# SCH_USB-Converter_2025-04-09.net
KiCad netlist of a schematic drawn in EasyEDA
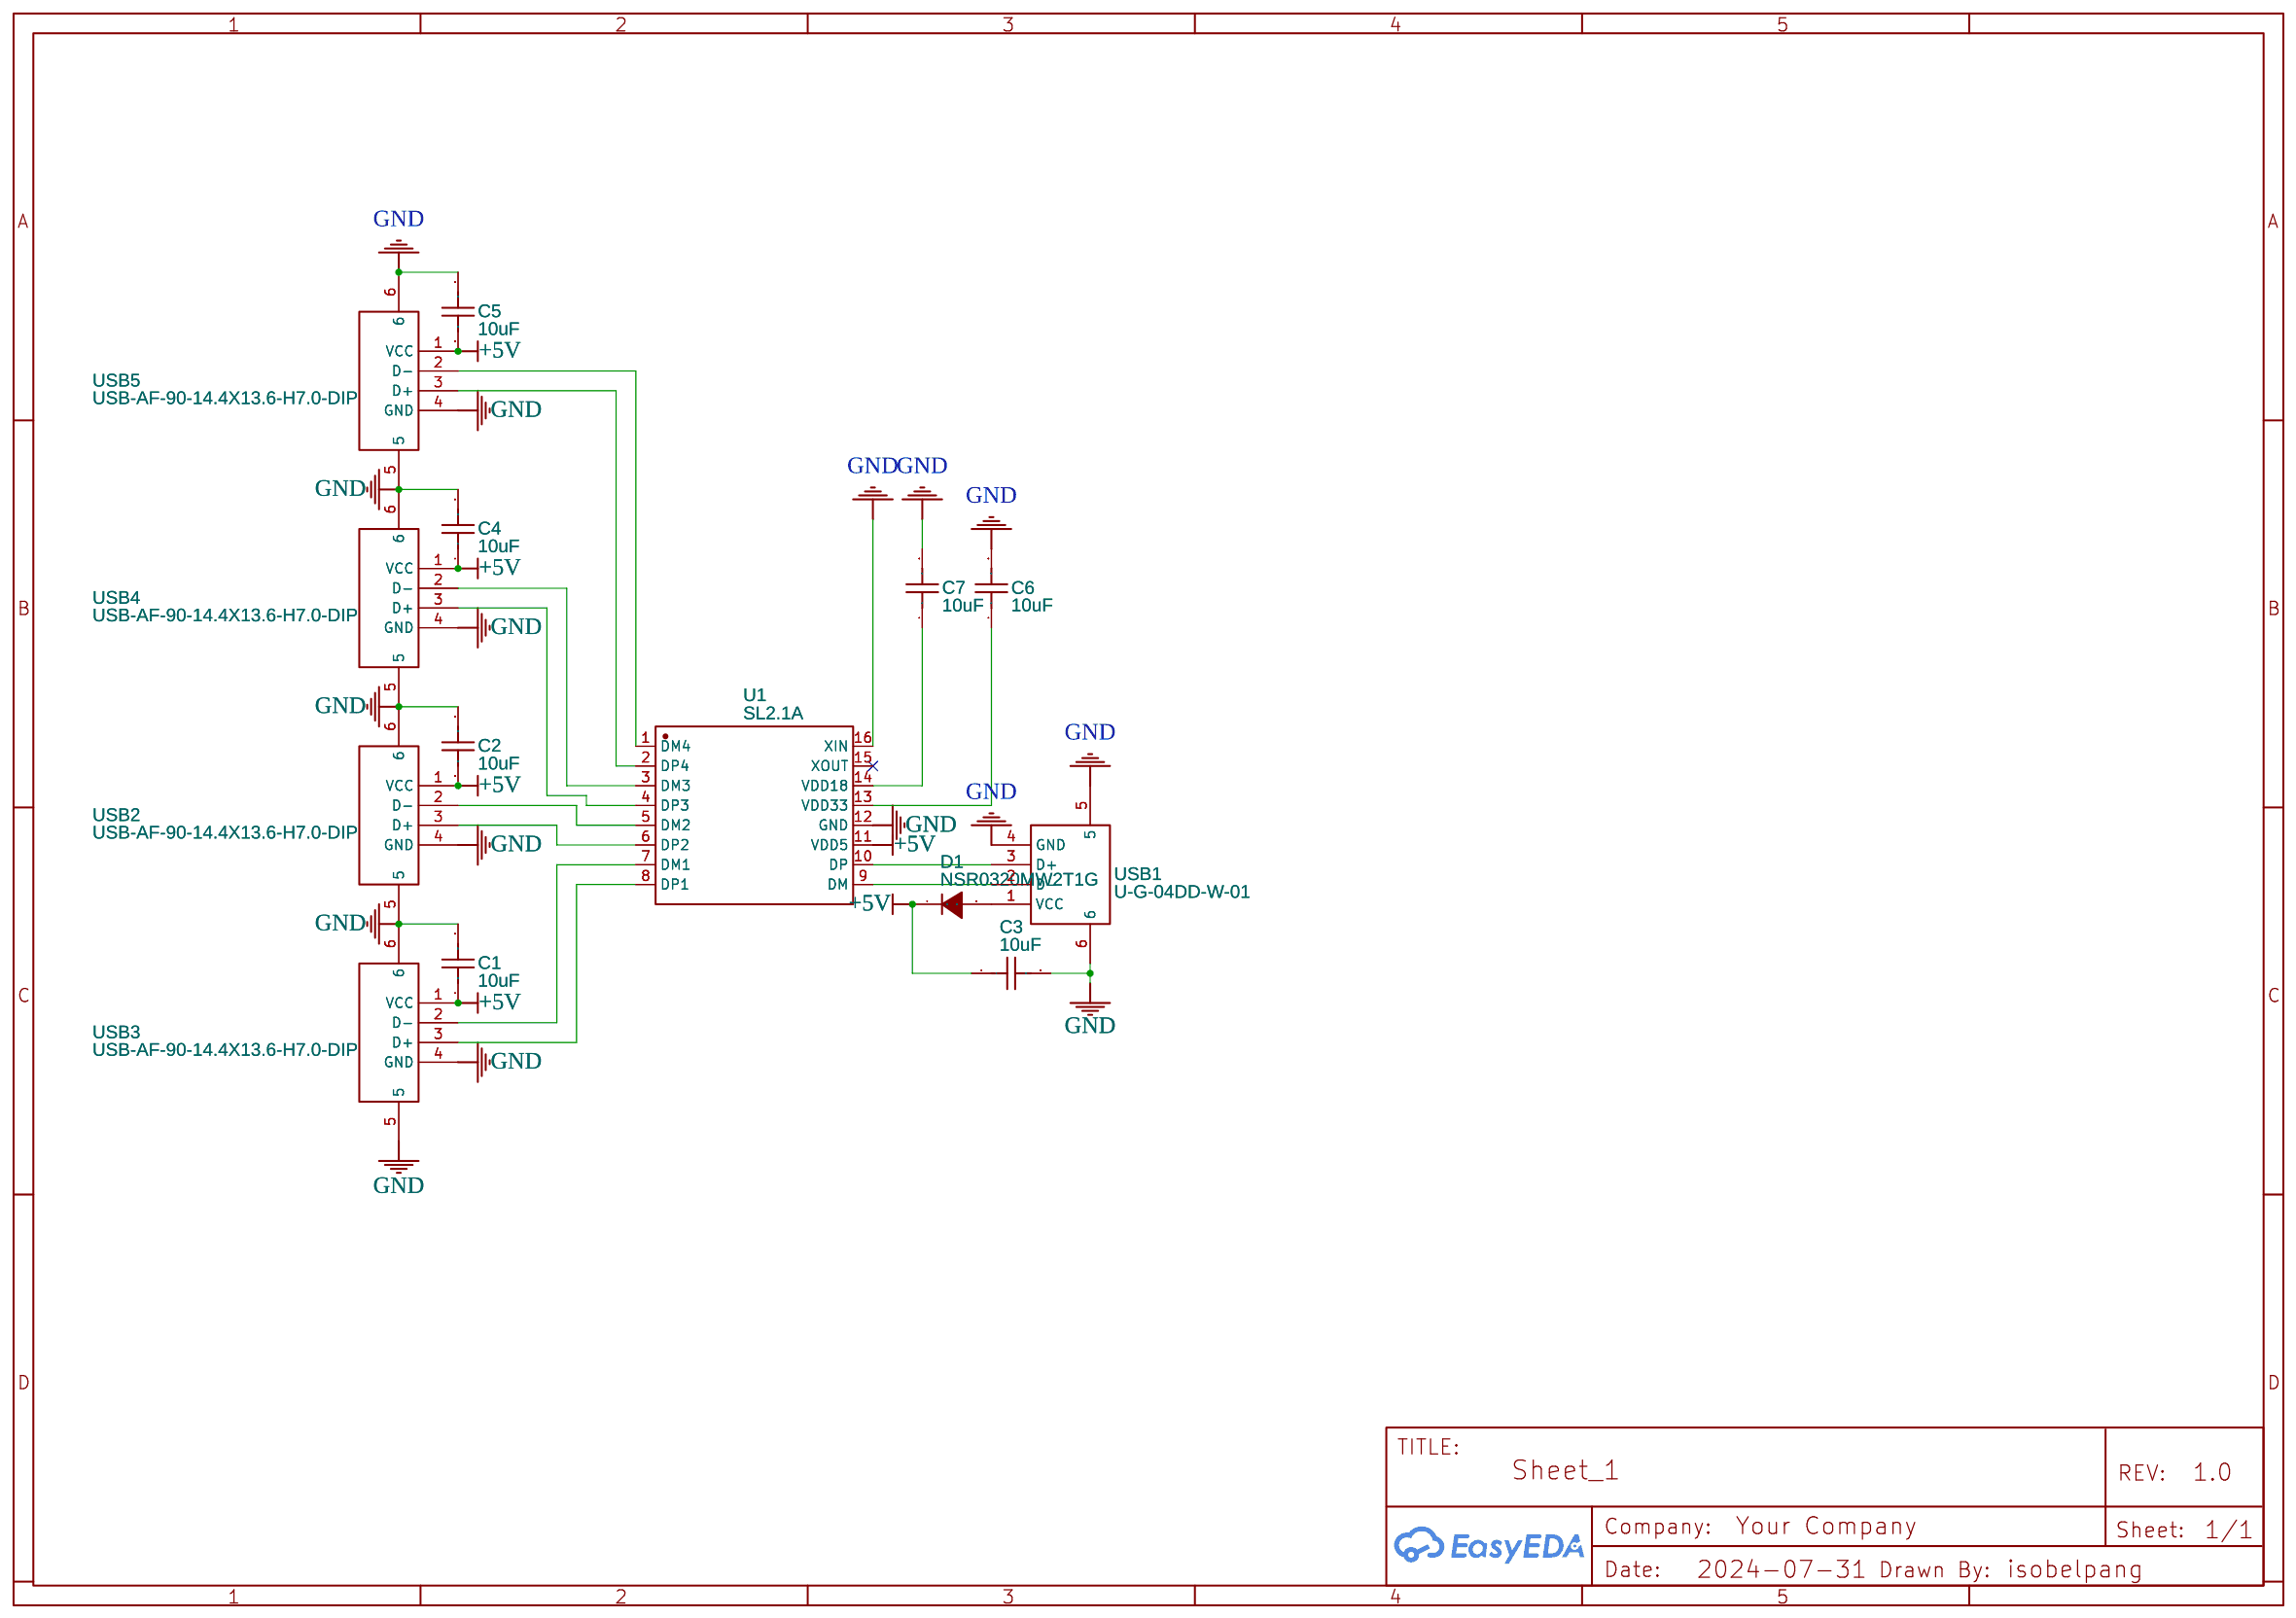
[diagram p0: schematic sheet]

(export (version "E")
  (design (tool "Eeschema 10.0.6"))
  (components
    (comp (ref "C1")
      (value "10uF")
      (fields
        (field (name "Manufacturer Part") "CL10A106KP8NNNC")
        (field (name "Manufacturer") "SAMSUNG(三星)")
      )
      (libsource (lib "") (part "CL10A106KP8NNNC"))
    )
    (comp (ref "C2")
      (value "10uF")
      (fields
        (field (name "Manufacturer Part") "CL10A106KP8NNNC")
        (field (name "Manufacturer") "SAMSUNG(三星)")
      )
      (libsource (lib "") (part "CL10A106KP8NNNC"))
    )
    (comp (ref "C3")
      (value "10uF")
      (fields
        (field (name "Manufacturer Part") "CL10A106KP8NNNC")
        (field (name "Manufacturer") "SAMSUNG(三星)")
      )
      (libsource (lib "") (part "CL10A106KP8NNNC_1"))
    )
    (comp (ref "C4")
      (value "10uF")
      (fields
        (field (name "Manufacturer Part") "CL10A106KP8NNNC")
        (field (name "Manufacturer") "SAMSUNG(三星)")
      )
      (libsource (lib "") (part "CL10A106KP8NNNC"))
    )
    (comp (ref "C5")
      (value "10uF")
      (fields
        (field (name "Manufacturer Part") "CL10A106KP8NNNC")
        (field (name "Manufacturer") "SAMSUNG(三星)")
      )
      (libsource (lib "") (part "CL10A106KP8NNNC_2"))
    )
    (comp (ref "C6")
      (value "10uF")
      (fields
        (field (name "Manufacturer Part") "CL10A106KP8NNNC")
        (field (name "Manufacturer") "SAMSUNG(三星)")
      )
      (libsource (lib "") (part "CL10A106KP8NNNC"))
    )
    (comp (ref "C7")
      (value "10uF")
      (fields
        (field (name "Manufacturer Part") "CL10A106KP8NNNC")
        (field (name "Manufacturer") "SAMSUNG(三星)")
      )
      (libsource (lib "") (part "CL10A106KP8NNNC"))
    )
    (comp (ref "D1")
      (value "NSR0320MW2T1G")
      (fields (field (name "Manufacturer") "onsemi(安森美)"))
      (libsource (lib "") (part "NSR0320MW2T1G"))
    )
    (comp (ref "U1")
      (value "SL2.1A")
      (fields (field (name "Manufacturer") "CoreChips(和芯润德)"))
      (libsource (lib "") (part "SL2.1A"))
    )
    (comp (ref "USB1")
      (value "U-G-04DD-W-01")
      (fields (field (name "Manufacturer Part") "U-G-O4DD-W-1") (field (name "Manufacturer") "韩国韩荣"))
      (libsource (lib "") (part "U-G-04DD-W-01"))
    )
    (comp (ref "USB2")
      (value "USB-AF-90-14.4X13.6-H7.0-DIP")
      (fields (field (name "Manufacturer Part") "903-131A1011D10100") (field (name "Manufacturer") "精拓金"))
      (libsource (lib "") (part "USB-AF-90-14.4X13.6-H7.0-DIP"))
    )
    (comp (ref "USB3")
      (value "USB-AF-90-14.4X13.6-H7.0-DIP")
      (fields (field (name "Manufacturer Part") "903-131A1011D10100") (field (name "Manufacturer") "精拓金"))
      (libsource (lib "") (part "USB-AF-90-14.4X13.6-H7.0-DIP"))
    )
    (comp (ref "USB4")
      (value "USB-AF-90-14.4X13.6-H7.0-DIP")
      (fields (field (name "Manufacturer Part") "903-131A1011D10100") (field (name "Manufacturer") "精拓金"))
      (libsource (lib "") (part "USB-AF-90-14.4X13.6-H7.0-DIP"))
    )
    (comp (ref "USB5")
      (value "USB-AF-90-14.4X13.6-H7.0-DIP")
      (fields (field (name "Manufacturer Part") "903-131A1011D10100") (field (name "Manufacturer") "精拓金"))
      (libsource (lib "") (part "USB-AF-90-14.4X13.6-H7.0-DIP"))
    )
  )
  (nets
    (net (code "1") (name "+5V") (class "Default")
      (node (ref "C1") (pin "1") (pinfunction "1_1") (pintype "unspecified"))
      (node (ref "C2") (pin "1") (pinfunction "1_1") (pintype "unspecified"))
      (node (ref "C3") (pin "1") (pinfunction "1_1") (pintype "unspecified"))
      (node (ref "C4") (pin "1") (pinfunction "1_1") (pintype "unspecified"))
      (node (ref "C5") (pin "2") (pinfunction "2_2") (pintype "unspecified"))
      (node (ref "D1") (pin "1") (pinfunction "C_1") (pintype "unspecified"))
      (node (ref "U1") (pin "11") (pinfunction "VDD5_11") (pintype "unspecified"))
      (node (ref "USB2") (pin "1") (pinfunction "VCC_1") (pintype "unspecified"))
      (node (ref "USB3") (pin "1") (pinfunction "VCC_1") (pintype "unspecified"))
      (node (ref "USB4") (pin "1") (pinfunction "VCC_1") (pintype "unspecified"))
      (node (ref "USB5") (pin "1") (pinfunction "VCC_1") (pintype "unspecified"))
    )
    (net (code "2") (name "GND") (class "Default")
      (node (ref "C1") (pin "2") (pinfunction "2_2") (pintype "unspecified"))
      (node (ref "C2") (pin "2") (pinfunction "2_2") (pintype "unspecified"))
      (node (ref "C3") (pin "2") (pinfunction "2_2") (pintype "unspecified"))
      (node (ref "C4") (pin "2") (pinfunction "2_2") (pintype "unspecified"))
      (node (ref "C5") (pin "1") (pinfunction "1_1") (pintype "unspecified"))
      (node (ref "C6") (pin "2") (pinfunction "2_2") (pintype "unspecified"))
      (node (ref "C7") (pin "2") (pinfunction "2_2") (pintype "unspecified"))
      (node (ref "U1") (pin "12") (pinfunction "GND_12") (pintype "unspecified"))
      (node (ref "U1") (pin "16") (pinfunction "XIN_16") (pintype "unspecified"))
      (node (ref "USB1") (pin "4") (pinfunction "GND_4") (pintype "unspecified"))
      (node (ref "USB1") (pin "5") (pinfunction "5_5") (pintype "unspecified"))
      (node (ref "USB1") (pin "6") (pinfunction "6_6") (pintype "unspecified"))
      (node (ref "USB2") (pin "4") (pinfunction "GND_4") (pintype "unspecified"))
      (node (ref "USB2") (pin "5") (pinfunction "5_5") (pintype "unspecified"))
      (node (ref "USB2") (pin "6") (pinfunction "6_6") (pintype "unspecified"))
      (node (ref "USB3") (pin "4") (pinfunction "GND_4") (pintype "unspecified"))
      (node (ref "USB3") (pin "5") (pinfunction "5_5") (pintype "unspecified"))
      (node (ref "USB3") (pin "6") (pinfunction "6_6") (pintype "unspecified"))
      (node (ref "USB4") (pin "4") (pinfunction "GND_4") (pintype "unspecified"))
      (node (ref "USB4") (pin "5") (pinfunction "5_5") (pintype "unspecified"))
      (node (ref "USB4") (pin "6") (pinfunction "6_6") (pintype "unspecified"))
      (node (ref "USB5") (pin "4") (pinfunction "GND_4") (pintype "unspecified"))
      (node (ref "USB5") (pin "5") (pinfunction "5_5") (pintype "unspecified"))
      (node (ref "USB5") (pin "6") (pinfunction "6_6") (pintype "unspecified"))
    )
    (net (code "3") (name "Net-(D1-A)") (class "Default")
      (node (ref "D1") (pin "2") (pinfunction "A_2") (pintype "unspecified"))
      (node (ref "USB1") (pin "1") (pinfunction "VCC_1") (pintype "unspecified"))
    )
    (net (code "4") (name "Net-(U1-DM)") (class "Default")
      (node (ref "U1") (pin "9") (pinfunction "DM_9") (pintype "unspecified"))
      (node (ref "USB1") (pin "2") (pinfunction "D-_2") (pintype "unspecified"))
    )
    (net (code "5") (name "Net-(U1-DM1)") (class "Default")
      (node (ref "U1") (pin "7") (pinfunction "DM1_7") (pintype "unspecified"))
      (node (ref "USB3") (pin "2") (pinfunction "D-_2") (pintype "unspecified"))
    )
    (net (code "6") (name "Net-(U1-DM2)") (class "Default")
      (node (ref "U1") (pin "5") (pinfunction "DM2_5") (pintype "unspecified"))
      (node (ref "USB2") (pin "2") (pinfunction "D-_2") (pintype "unspecified"))
    )
    (net (code "7") (name "Net-(U1-DM3)") (class "Default")
      (node (ref "U1") (pin "3") (pinfunction "DM3_3") (pintype "unspecified"))
      (node (ref "USB4") (pin "2") (pinfunction "D-_2") (pintype "unspecified"))
    )
    (net (code "8") (name "Net-(U1-DM4)") (class "Default")
      (node (ref "U1") (pin "1") (pinfunction "DM4_1") (pintype "unspecified"))
      (node (ref "USB5") (pin "2") (pinfunction "D-_2") (pintype "unspecified"))
    )
    (net (code "9") (name "Net-(U1-DP)") (class "Default")
      (node (ref "U1") (pin "10") (pinfunction "DP_10") (pintype "unspecified"))
      (node (ref "USB1") (pin "3") (pinfunction "D+_3") (pintype "unspecified"))
    )
    (net (code "10") (name "Net-(U1-DP1)") (class "Default")
      (node (ref "U1") (pin "8") (pinfunction "DP1_8") (pintype "unspecified"))
      (node (ref "USB3") (pin "3") (pinfunction "D+_3") (pintype "unspecified"))
    )
    (net (code "11") (name "Net-(U1-DP2)") (class "Default")
      (node (ref "U1") (pin "6") (pinfunction "DP2_6") (pintype "unspecified"))
      (node (ref "USB2") (pin "3") (pinfunction "D+_3") (pintype "unspecified"))
    )
    (net (code "12") (name "Net-(U1-DP3)") (class "Default")
      (node (ref "U1") (pin "4") (pinfunction "DP3_4") (pintype "unspecified"))
      (node (ref "USB4") (pin "3") (pinfunction "D+_3") (pintype "unspecified"))
    )
    (net (code "13") (name "Net-(U1-DP4)") (class "Default")
      (node (ref "U1") (pin "2") (pinfunction "DP4_2") (pintype "unspecified"))
      (node (ref "USB5") (pin "3") (pinfunction "D+_3") (pintype "unspecified"))
    )
    (net (code "14") (name "Net-(U1-VDD18)") (class "Default")
      (node (ref "C7") (pin "1") (pinfunction "1_1") (pintype "unspecified"))
      (node (ref "U1") (pin "14") (pinfunction "VDD18_14") (pintype "unspecified"))
    )
    (net (code "15") (name "Net-(U1-VDD33)") (class "Default")
      (node (ref "C6") (pin "1") (pinfunction "1_1") (pintype "unspecified"))
      (node (ref "U1") (pin "13") (pinfunction "VDD33_13") (pintype "unspecified"))
    )
    (net (code "16") (name "unconnected-(U1-XOUT-Pad15)") (class "Default")
      (node (ref "U1") (pin "15") (pinfunction "XOUT_15") (pintype "unspecified+no_connect"))
    )
  )
)
